# Mechanical.net
KiCad netlist of a schematic drawn in Altium Designer
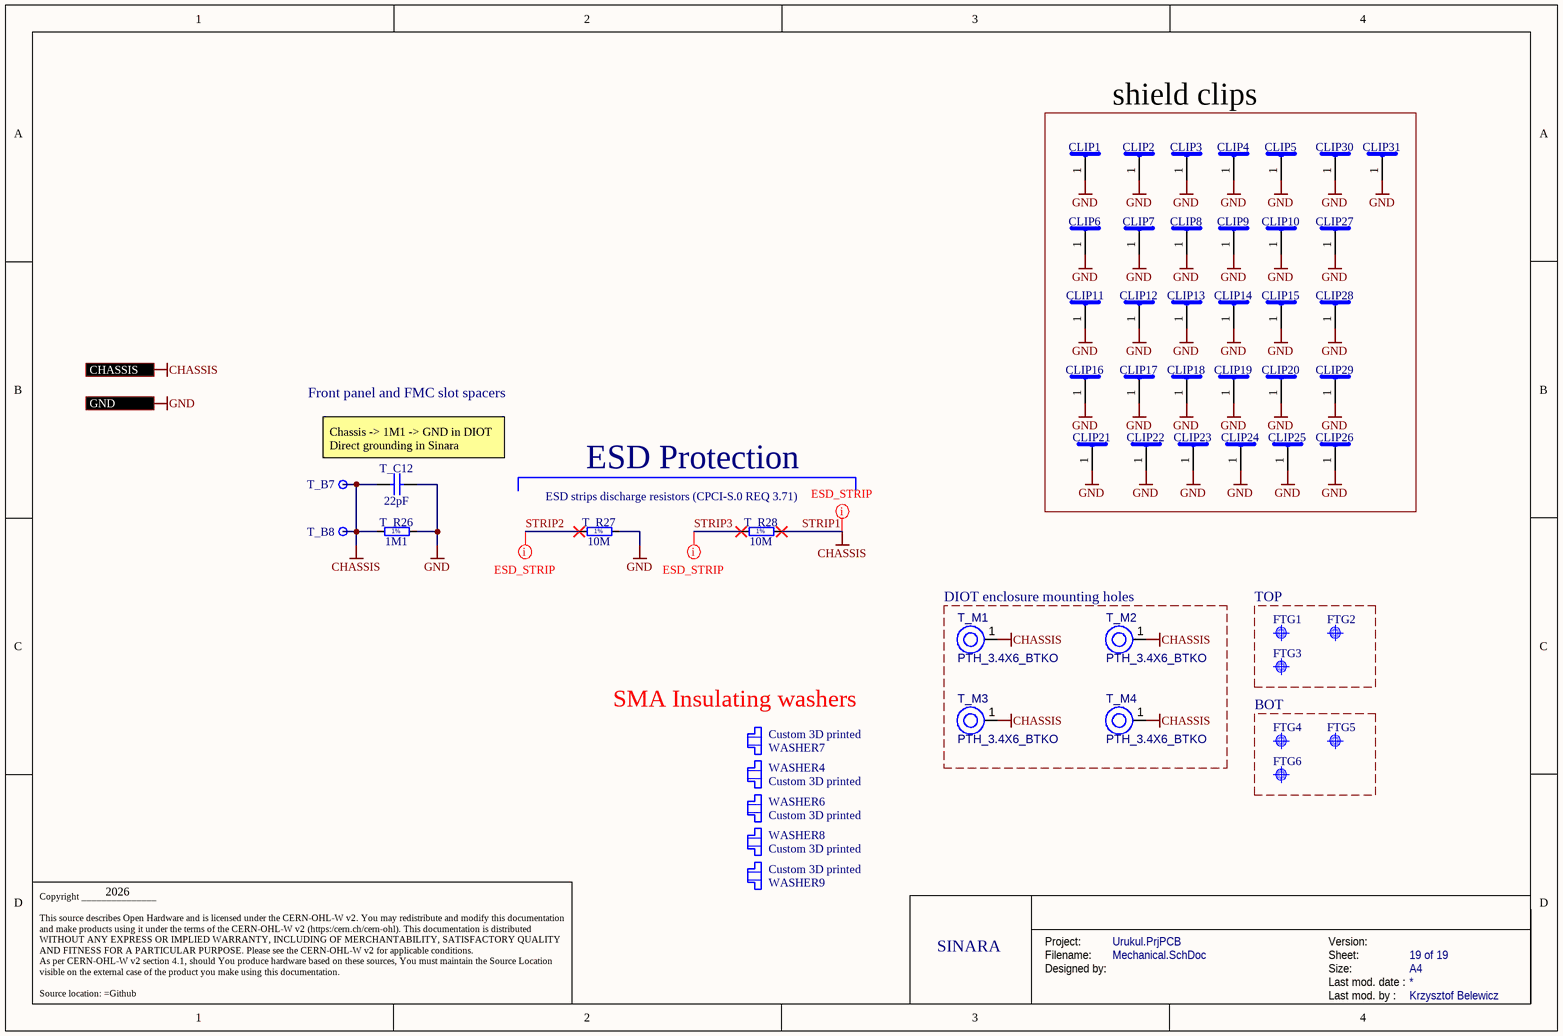
[diagram p0: Mechanical.SchDoc]

(export (version "E")
  (design (tool "Eeschema 10.0.6"))
  (components
    (comp (ref "CLIP1")
      (value "S1411-46R")
      (footprint "CLIP_HOLLAND-SHIELDING_LC")
      (description "Surface Mount Clip for PCB Screening Covers")
      (fields (field (name "MANUFACTURER") "HARWIN") (field (name "AUTHOR") "CERN DEM JLC"))
      (libsource (lib "LIBRARY_SCH") (part "SHIELD_CLIP"))
    )
    (comp (ref "CLIP2")
      (value "S1411-46R")
      (footprint "CLIP_HOLLAND-SHIELDING_LC")
      (description "Surface Mount Clip for PCB Screening Covers")
      (fields (field (name "MANUFACTURER") "HARWIN") (field (name "AUTHOR") "CERN DEM JLC"))
      (libsource (lib "LIBRARY_SCH") (part "SHIELD_CLIP"))
    )
    (comp (ref "CLIP3")
      (value "S1411-46R")
      (footprint "CLIP_HOLLAND-SHIELDING_LC")
      (description "Surface Mount Clip for PCB Screening Covers")
      (fields (field (name "MANUFACTURER") "HARWIN") (field (name "AUTHOR") "CERN DEM JLC"))
      (libsource (lib "LIBRARY_SCH") (part "SHIELD_CLIP"))
    )
    (comp (ref "CLIP4")
      (value "S1411-46R")
      (footprint "CLIP_HOLLAND-SHIELDING_LC")
      (description "Surface Mount Clip for PCB Screening Covers")
      (fields (field (name "MANUFACTURER") "HARWIN") (field (name "AUTHOR") "CERN DEM JLC"))
      (libsource (lib "LIBRARY_SCH") (part "SHIELD_CLIP"))
    )
    (comp (ref "CLIP5")
      (value "S1411-46R")
      (footprint "CLIP_HOLLAND-SHIELDING_LC")
      (description "Surface Mount Clip for PCB Screening Covers")
      (fields (field (name "MANUFACTURER") "HARWIN") (field (name "AUTHOR") "CERN DEM JLC"))
      (libsource (lib "LIBRARY_SCH") (part "SHIELD_CLIP"))
    )
    (comp (ref "CLIP6")
      (value "S1411-46R")
      (footprint "CLIP_HOLLAND-SHIELDING_LC")
      (description "Surface Mount Clip for PCB Screening Covers")
      (fields (field (name "MANUFACTURER") "HARWIN") (field (name "AUTHOR") "CERN DEM JLC"))
      (libsource (lib "LIBRARY_SCH") (part "SHIELD_CLIP"))
    )
    (comp (ref "CLIP7")
      (value "S1411-46R")
      (footprint "CLIP_HOLLAND-SHIELDING_LC")
      (description "Surface Mount Clip for PCB Screening Covers")
      (fields (field (name "MANUFACTURER") "HARWIN") (field (name "AUTHOR") "CERN DEM JLC"))
      (libsource (lib "LIBRARY_SCH") (part "SHIELD_CLIP"))
    )
    (comp (ref "CLIP8")
      (value "S1411-46R")
      (footprint "CLIP_HOLLAND-SHIELDING_LC")
      (description "Surface Mount Clip for PCB Screening Covers")
      (fields (field (name "MANUFACTURER") "HARWIN") (field (name "AUTHOR") "CERN DEM JLC"))
      (libsource (lib "LIBRARY_SCH") (part "SHIELD_CLIP"))
    )
    (comp (ref "CLIP9")
      (value "S1411-46R")
      (footprint "CLIP_HOLLAND-SHIELDING_LC")
      (description "Surface Mount Clip for PCB Screening Covers")
      (fields (field (name "MANUFACTURER") "HARWIN") (field (name "AUTHOR") "CERN DEM JLC"))
      (libsource (lib "LIBRARY_SCH") (part "SHIELD_CLIP"))
    )
    (comp (ref "CLIP10")
      (value "S1411-46R")
      (footprint "CLIP_HOLLAND-SHIELDING_LC")
      (description "Surface Mount Clip for PCB Screening Covers")
      (fields (field (name "MANUFACTURER") "HARWIN") (field (name "AUTHOR") "CERN DEM JLC"))
      (libsource (lib "LIBRARY_SCH") (part "SHIELD_CLIP"))
    )
    (comp (ref "CLIP11")
      (value "S1411-46R")
      (footprint "CLIP_HOLLAND-SHIELDING_LC")
      (description "Surface Mount Clip for PCB Screening Covers")
      (fields (field (name "MANUFACTURER") "HARWIN") (field (name "AUTHOR") "CERN DEM JLC"))
      (libsource (lib "LIBRARY_SCH") (part "SHIELD_CLIP"))
    )
    (comp (ref "CLIP12")
      (value "S1411-46R")
      (footprint "CLIP_HOLLAND-SHIELDING_LC")
      (description "Surface Mount Clip for PCB Screening Covers")
      (fields (field (name "MANUFACTURER") "HARWIN") (field (name "AUTHOR") "CERN DEM JLC"))
      (libsource (lib "LIBRARY_SCH") (part "SHIELD_CLIP"))
    )
    (comp (ref "CLIP13")
      (value "S1411-46R")
      (footprint "CLIP_HOLLAND-SHIELDING_LC")
      (description "Surface Mount Clip for PCB Screening Covers")
      (fields (field (name "MANUFACTURER") "HARWIN") (field (name "AUTHOR") "CERN DEM JLC"))
      (libsource (lib "LIBRARY_SCH") (part "SHIELD_CLIP"))
    )
    (comp (ref "CLIP14")
      (value "S1411-46R")
      (footprint "CLIP_HOLLAND-SHIELDING_LC")
      (description "Surface Mount Clip for PCB Screening Covers")
      (fields (field (name "MANUFACTURER") "HARWIN") (field (name "AUTHOR") "CERN DEM JLC"))
      (libsource (lib "LIBRARY_SCH") (part "SHIELD_CLIP"))
    )
    (comp (ref "CLIP15")
      (value "S1411-46R")
      (footprint "CLIP_HOLLAND-SHIELDING_LC")
      (description "Surface Mount Clip for PCB Screening Covers")
      (fields (field (name "MANUFACTURER") "HARWIN") (field (name "AUTHOR") "CERN DEM JLC"))
      (libsource (lib "LIBRARY_SCH") (part "SHIELD_CLIP"))
    )
    (comp (ref "CLIP16")
      (value "S1411-46R")
      (footprint "CLIP_HOLLAND-SHIELDING_LC")
      (description "Surface Mount Clip for PCB Screening Covers")
      (fields (field (name "MANUFACTURER") "HARWIN") (field (name "AUTHOR") "CERN DEM JLC"))
      (libsource (lib "LIBRARY_SCH") (part "SHIELD_CLIP"))
    )
    (comp (ref "CLIP17")
      (value "S1411-46R")
      (footprint "CLIP_HOLLAND-SHIELDING_LC")
      (description "Surface Mount Clip for PCB Screening Covers")
      (fields (field (name "MANUFACTURER") "HARWIN") (field (name "AUTHOR") "CERN DEM JLC"))
      (libsource (lib "LIBRARY_SCH") (part "SHIELD_CLIP"))
    )
    (comp (ref "CLIP18")
      (value "S1411-46R")
      (footprint "CLIP_HOLLAND-SHIELDING_LC")
      (description "Surface Mount Clip for PCB Screening Covers")
      (fields (field (name "MANUFACTURER") "HARWIN") (field (name "AUTHOR") "CERN DEM JLC"))
      (libsource (lib "LIBRARY_SCH") (part "SHIELD_CLIP"))
    )
    (comp (ref "CLIP19")
      (value "S1411-46R")
      (footprint "CLIP_HOLLAND-SHIELDING_LC")
      (description "Surface Mount Clip for PCB Screening Covers")
      (fields (field (name "MANUFACTURER") "HARWIN") (field (name "AUTHOR") "CERN DEM JLC"))
      (libsource (lib "LIBRARY_SCH") (part "SHIELD_CLIP"))
    )
    (comp (ref "CLIP20")
      (value "S1411-46R")
      (footprint "CLIP_HOLLAND-SHIELDING_LC")
      (description "Surface Mount Clip for PCB Screening Covers")
      (fields (field (name "MANUFACTURER") "HARWIN") (field (name "AUTHOR") "CERN DEM JLC"))
      (libsource (lib "LIBRARY_SCH") (part "SHIELD_CLIP"))
    )
    (comp (ref "CLIP21")
      (value "S1411-46R")
      (footprint "CLIP_HOLLAND-SHIELDING_LC")
      (description "Surface Mount Clip for PCB Screening Covers")
      (fields (field (name "MANUFACTURER") "HARWIN") (field (name "AUTHOR") "CERN DEM JLC"))
      (libsource (lib "LIBRARY_SCH") (part "SHIELD_CLIP"))
    )
    (comp (ref "CLIP22")
      (value "S1411-46R")
      (footprint "CLIP_HOLLAND-SHIELDING_LC")
      (description "Surface Mount Clip for PCB Screening Covers")
      (fields (field (name "MANUFACTURER") "HARWIN") (field (name "AUTHOR") "CERN DEM JLC"))
      (libsource (lib "LIBRARY_SCH") (part "SHIELD_CLIP"))
    )
    (comp (ref "CLIP23")
      (value "S1411-46R")
      (footprint "CLIP_HOLLAND-SHIELDING_LC")
      (description "Surface Mount Clip for PCB Screening Covers")
      (fields (field (name "MANUFACTURER") "HARWIN") (field (name "AUTHOR") "CERN DEM JLC"))
      (libsource (lib "LIBRARY_SCH") (part "SHIELD_CLIP"))
    )
    (comp (ref "CLIP24")
      (value "S1411-46R")
      (footprint "CLIP_HOLLAND-SHIELDING_LC")
      (description "Surface Mount Clip for PCB Screening Covers")
      (fields (field (name "MANUFACTURER") "HARWIN") (field (name "AUTHOR") "CERN DEM JLC"))
      (libsource (lib "LIBRARY_SCH") (part "SHIELD_CLIP"))
    )
    (comp (ref "CLIP25")
      (value "S1411-46R")
      (footprint "CLIP_HOLLAND-SHIELDING_LC")
      (description "Surface Mount Clip for PCB Screening Covers")
      (fields (field (name "MANUFACTURER") "HARWIN") (field (name "AUTHOR") "CERN DEM JLC"))
      (libsource (lib "LIBRARY_SCH") (part "SHIELD_CLIP"))
    )
    (comp (ref "CLIP26")
      (value "S1411-46R")
      (footprint "CLIP_HOLLAND-SHIELDING_LC")
      (description "Surface Mount Clip for PCB Screening Covers")
      (fields (field (name "MANUFACTURER") "HARWIN") (field (name "AUTHOR") "CERN DEM JLC"))
      (libsource (lib "LIBRARY_SCH") (part "SHIELD_CLIP"))
    )
    (comp (ref "CLIP27")
      (value "S1411-46R")
      (footprint "CLIP_HOLLAND-SHIELDING_LC")
      (description "Surface Mount Clip for PCB Screening Covers")
      (fields (field (name "MANUFACTURER") "HARWIN") (field (name "AUTHOR") "CERN DEM JLC"))
      (libsource (lib "LIBRARY_SCH") (part "SHIELD_CLIP"))
    )
    (comp (ref "CLIP28")
      (value "S1411-46R")
      (footprint "CLIP_HOLLAND-SHIELDING_LC")
      (description "Surface Mount Clip for PCB Screening Covers")
      (fields (field (name "MANUFACTURER") "HARWIN") (field (name "AUTHOR") "CERN DEM JLC"))
      (libsource (lib "LIBRARY_SCH") (part "SHIELD_CLIP"))
    )
    (comp (ref "CLIP29")
      (value "S1411-46R")
      (footprint "CLIP_HOLLAND-SHIELDING_LC")
      (description "Surface Mount Clip for PCB Screening Covers")
      (fields (field (name "MANUFACTURER") "HARWIN") (field (name "AUTHOR") "CERN DEM JLC"))
      (libsource (lib "LIBRARY_SCH") (part "SHIELD_CLIP"))
    )
    (comp (ref "CLIP30")
      (value "S1411-46R")
      (footprint "CLIP_HOLLAND-SHIELDING_LC")
      (description "Surface Mount Clip for PCB Screening Covers")
      (fields (field (name "MANUFACTURER") "HARWIN") (field (name "AUTHOR") "CERN DEM JLC"))
      (libsource (lib "LIBRARY_SCH") (part "SHIELD_CLIP"))
    )
    (comp (ref "CLIP31")
      (value "S1411-46R")
      (footprint "CLIP_HOLLAND-SHIELDING_LC")
      (description "Surface Mount Clip for PCB Screening Covers")
      (fields (field (name "MANUFACTURER") "HARWIN") (field (name "AUTHOR") "CERN DEM JLC"))
      (libsource (lib "LIBRARY_SCH") (part "SHIELD_CLIP"))
    )
    (comp (ref "FTG1")
      (value "Use only in PCB")
      (footprint "FIDUCIAL_TOP_C100-200")
      (description "Fiducial Target")
      (fields (field (name "PART NUMBER") "FIDUCIAL_TARGET_C100-200") (field (name "AUTHOR") "CERN DEM JLC"))
      (libsource (lib "Eletro-mechanical") (part "Fiducial Target"))
    )
    (comp (ref "FTG2")
      (value "Use only in PCB")
      (footprint "FIDUCIAL_TOP_S100-200")
      (description "Fiducial Target")
      (fields (field (name "PART NUMBER") "FIDUCIAL_TARGET_S100-200") (field (name "AUTHOR") "CERN DEM JLC"))
      (libsource (lib "Eletro-mechanical") (part "Fiducial Target"))
    )
    (comp (ref "FTG3")
      (value "Use only in PCB")
      (footprint "FIDUCIAL_TOP_S100-200")
      (description "Fiducial Target")
      (fields (field (name "PART NUMBER") "FIDUCIAL_TARGET_S100-200") (field (name "AUTHOR") "CERN DEM JLC"))
      (libsource (lib "Eletro-mechanical") (part "Fiducial Target"))
    )
    (comp (ref "FTG4")
      (value "Use only in PCB")
      (footprint "FIDUCIAL_TOP_C100-200")
      (description "Fiducial Target")
      (fields (field (name "PART NUMBER") "FIDUCIAL_TARGET_C100-200") (field (name "AUTHOR") "CERN DEM JLC"))
      (libsource (lib "Eletro-mechanical") (part "Fiducial Target"))
    )
    (comp (ref "FTG5")
      (value "Use only in PCB")
      (footprint "FIDUCIAL_TOP_S100-200")
      (description "Fiducial Target")
      (fields (field (name "PART NUMBER") "FIDUCIAL_TARGET_S100-200") (field (name "AUTHOR") "CERN DEM JLC"))
      (libsource (lib "Eletro-mechanical") (part "Fiducial Target"))
    )
    (comp (ref "FTG6")
      (value "Use only in PCB")
      (footprint "FIDUCIAL_TOP_S100-200")
      (description "Fiducial Target")
      (fields (field (name "PART NUMBER") "FIDUCIAL_TARGET_S100-200") (field (name "AUTHOR") "CERN DEM JLC"))
      (libsource (lib "Eletro-mechanical") (part "Fiducial Target"))
    )
    (comp (ref "T_B7")
      (value "Plated Hole")
      (footprint "c600h270")
      (description "Single Terminal Socket")
      (fields (field (name "PART NUMBER") "PLATED_HOLE2.7_PAD6.0") (field (name "AUTHOR") "CERN DEM HF"))
      (libsource (lib "Eletro-mechanical") (part "Single Terminal Socket"))
    )
    (comp (ref "T_B8")
      (value "Plated Hole")
      (footprint "c600h270")
      (description "Single Terminal Socket")
      (fields (field (name "PART NUMBER") "PLATED_HOLE2.7_PAD6.0") (field (name "AUTHOR") "CERN DEM HF"))
      (libsource (lib "Eletro-mechanical") (part "Single Terminal Socket"))
    )
    (comp (ref "T_C12")
      (value "22pF")
      (footprint "CAPC1005X55N")
      (description "Non-polarised capacitor")
      (fields
        (field (name "PART NUMBER") "CC0402_22PF_50V_5%_C0G")
        (field (name "VOLTAGE") "50V")
        (field (name "AUTHOR") "CERN DEM JLC")
      )
      (libsource (lib "Capacitors") (part "Capacitor - non polarized"))
    )
    (comp (ref "T_M1")
      (value "PTH_3.4X6_BTKO")
      (footprint "PTH-M3.4x6.0_BTKO")
      (description "PTH  Hole 3.4, 6mm pad")
      (libsource (lib "TechnoSystem Workspace") (part "PTH3.4x6.0_BTKO"))
    )
    (comp (ref "T_M2")
      (value "PTH_3.4X6_BTKO")
      (footprint "PTH-M3.4x6.0_BTKO")
      (description "PTH  Hole 3.4, 6mm pad")
      (libsource (lib "TechnoSystem Workspace") (part "PTH3.4x6.0_BTKO"))
    )
    (comp (ref "T_M3")
      (value "PTH_3.4X6_BTKO")
      (footprint "PTH-M3.4x6.0_BTKO")
      (description "PTH  Hole 3.4, 6mm pad")
      (libsource (lib "TechnoSystem Workspace") (part "PTH3.4x6.0_BTKO"))
    )
    (comp (ref "T_M4")
      (value "PTH_3.4X6_BTKO")
      (footprint "PTH-M3.4x6.0_BTKO")
      (description "PTH  Hole 3.4, 6mm pad")
      (libsource (lib "TechnoSystem Workspace") (part "PTH3.4x6.0_BTKO"))
    )
    (comp (ref "T_R26")
      (value "1M1")
      (footprint "RESC2012X60N")
      (description "Resistor - 1%")
      (fields
        (field (name "PART NUMBER") "R0805_1M1_1%_0.125W_100PPM")
        (field (name "MANUFACTURER") "GENERIC")
        (field (name "AUTHOR") "CERN DEM JLC")
      )
      (libsource (lib "Resistors") (part "Resistor - 1%"))
    )
    (comp (ref "T_R27")
      (value "10M")
      (footprint "RESC2113X55N")
      (description "Resistor - 1%")
      (fields
        (field (name "PART NUMBER") "R0805_10M_1%_0.125W_100PPM_VISHAY_CRCW e3")
        (field (name "POWER") "0.125W")
        (field (name "AUTHOR") "CERN DEM BC")
      )
      (libsource (lib "Resistors") (part "Resistor - 1%"))
    )
    (comp (ref "T_R28")
      (value "10M")
      (footprint "RESC2113X55N")
      (description "Resistor - 1%")
      (fields
        (field (name "PART NUMBER") "R0805_10M_1%_0.125W_100PPM_VISHAY_CRCW e3")
        (field (name "POWER") "0.125W")
        (field (name "AUTHOR") "CERN DEM BC")
      )
      (libsource (lib "Resistors") (part "Resistor - 1%"))
    )
    (comp (ref "WASHER4")
      (value "Custom 3D printed")
      (footprint "Keystone_7687")
      (description "SMA_Shoulder Washer")
      (fields (field (name "AUTHOR") "GK"))
      (libsource (lib "LIBRARY_SCH") (part "Keystone_7687"))
    )
    (comp (ref "WASHER6")
      (value "Custom 3D printed")
      (footprint "Keystone_7687")
      (description "SMA_Shoulder Washer")
      (fields (field (name "AUTHOR") "GK"))
      (libsource (lib "LIBRARY_SCH") (part "Keystone_7687"))
    )
    (comp (ref "WASHER7")
      (value "Custom 3D printed")
      (footprint "Keystone_7687")
      (description "SMA_Shoulder Washer")
      (fields (field (name "AUTHOR") "GK"))
      (libsource (lib "LIBRARY_SCH") (part "Keystone_7687"))
    )
    (comp (ref "WASHER8")
      (value "Custom 3D printed")
      (footprint "Keystone_7687")
      (description "SMA_Shoulder Washer")
      (fields (field (name "AUTHOR") "GK"))
      (libsource (lib "LIBRARY_SCH") (part "Keystone_7687"))
    )
    (comp (ref "WASHER9")
      (value "Custom 3D printed")
      (footprint "Keystone_7687")
      (description "SMA_Shoulder Washer")
      (fields (field (name "AUTHOR") "GK"))
      (libsource (lib "LIBRARY_SCH") (part "Keystone_7687"))
    )
  )
  (nets
    (net (code "1") (name "/STRIP2") (class "Default")
      (node (ref "T_R27") (pin "1") (pinfunction "1_1") (pintype "passive+no_connect"))
    )
    (net (code "2") (name "/STRIP3") (class "Default")
      (node (ref "T_R28") (pin "1") (pinfunction "1_1") (pintype "passive+no_connect"))
    )
    (net (code "3") (name "CHASSIS") (class "Default")
      (node (ref "T_B7") (pin "1") (pinfunction "1_1") (pintype "bidirectional"))
      (node (ref "T_B8") (pin "1") (pinfunction "1_1") (pintype "bidirectional"))
      (node (ref "T_C12") (pin "1") (pinfunction "1_1") (pintype "passive"))
      (node (ref "T_M1") (pin "1") (pinfunction "H1_1") (pintype "passive"))
      (node (ref "T_M2") (pin "1") (pinfunction "H1_1") (pintype "passive"))
      (node (ref "T_M3") (pin "1") (pinfunction "H1_1") (pintype "passive"))
      (node (ref "T_M4") (pin "1") (pinfunction "H1_1") (pintype "passive"))
      (node (ref "T_R26") (pin "1") (pinfunction "1_1") (pintype "passive"))
      (node (ref "T_R28") (pin "2") (pinfunction "2_2") (pintype "passive"))
    )
    (net (code "4") (name "GND") (class "Default")
      (node (ref "CLIP1") (pin "1") (pinfunction "1_1") (pintype "passive"))
      (node (ref "CLIP10") (pin "1") (pinfunction "1_1") (pintype "passive"))
      (node (ref "CLIP11") (pin "1") (pinfunction "1_1") (pintype "passive"))
      (node (ref "CLIP12") (pin "1") (pinfunction "1_1") (pintype "passive"))
      (node (ref "CLIP13") (pin "1") (pinfunction "1_1") (pintype "passive"))
      (node (ref "CLIP14") (pin "1") (pinfunction "1_1") (pintype "passive"))
      (node (ref "CLIP15") (pin "1") (pinfunction "1_1") (pintype "passive"))
      (node (ref "CLIP16") (pin "1") (pinfunction "1_1") (pintype "passive"))
      (node (ref "CLIP17") (pin "1") (pinfunction "1_1") (pintype "passive"))
      (node (ref "CLIP18") (pin "1") (pinfunction "1_1") (pintype "passive"))
      (node (ref "CLIP19") (pin "1") (pinfunction "1_1") (pintype "passive"))
      (node (ref "CLIP2") (pin "1") (pinfunction "1_1") (pintype "passive"))
      (node (ref "CLIP20") (pin "1") (pinfunction "1_1") (pintype "passive"))
      (node (ref "CLIP21") (pin "1") (pinfunction "1_1") (pintype "passive"))
      (node (ref "CLIP22") (pin "1") (pinfunction "1_1") (pintype "passive"))
      (node (ref "CLIP23") (pin "1") (pinfunction "1_1") (pintype "passive"))
      (node (ref "CLIP24") (pin "1") (pinfunction "1_1") (pintype "passive"))
      (node (ref "CLIP25") (pin "1") (pinfunction "1_1") (pintype "passive"))
      (node (ref "CLIP26") (pin "1") (pinfunction "1_1") (pintype "passive"))
      (node (ref "CLIP27") (pin "1") (pinfunction "1_1") (pintype "passive"))
      (node (ref "CLIP28") (pin "1") (pinfunction "1_1") (pintype "passive"))
      (node (ref "CLIP29") (pin "1") (pinfunction "1_1") (pintype "passive"))
      (node (ref "CLIP3") (pin "1") (pinfunction "1_1") (pintype "passive"))
      (node (ref "CLIP30") (pin "1") (pinfunction "1_1") (pintype "passive"))
      (node (ref "CLIP31") (pin "1") (pinfunction "1_1") (pintype "passive"))
      (node (ref "CLIP4") (pin "1") (pinfunction "1_1") (pintype "passive"))
      (node (ref "CLIP5") (pin "1") (pinfunction "1_1") (pintype "passive"))
      (node (ref "CLIP6") (pin "1") (pinfunction "1_1") (pintype "passive"))
      (node (ref "CLIP7") (pin "1") (pinfunction "1_1") (pintype "passive"))
      (node (ref "CLIP8") (pin "1") (pinfunction "1_1") (pintype "passive"))
      (node (ref "CLIP9") (pin "1") (pinfunction "1_1") (pintype "passive"))
      (node (ref "T_C12") (pin "2") (pinfunction "2_2") (pintype "passive"))
      (node (ref "T_R26") (pin "2") (pinfunction "2_2") (pintype "passive"))
      (node (ref "T_R27") (pin "2") (pinfunction "2_2") (pintype "passive"))
    )
  )
)
